# Sheet2.net
KiCad netlist of a schematic drawn in Altium Designer
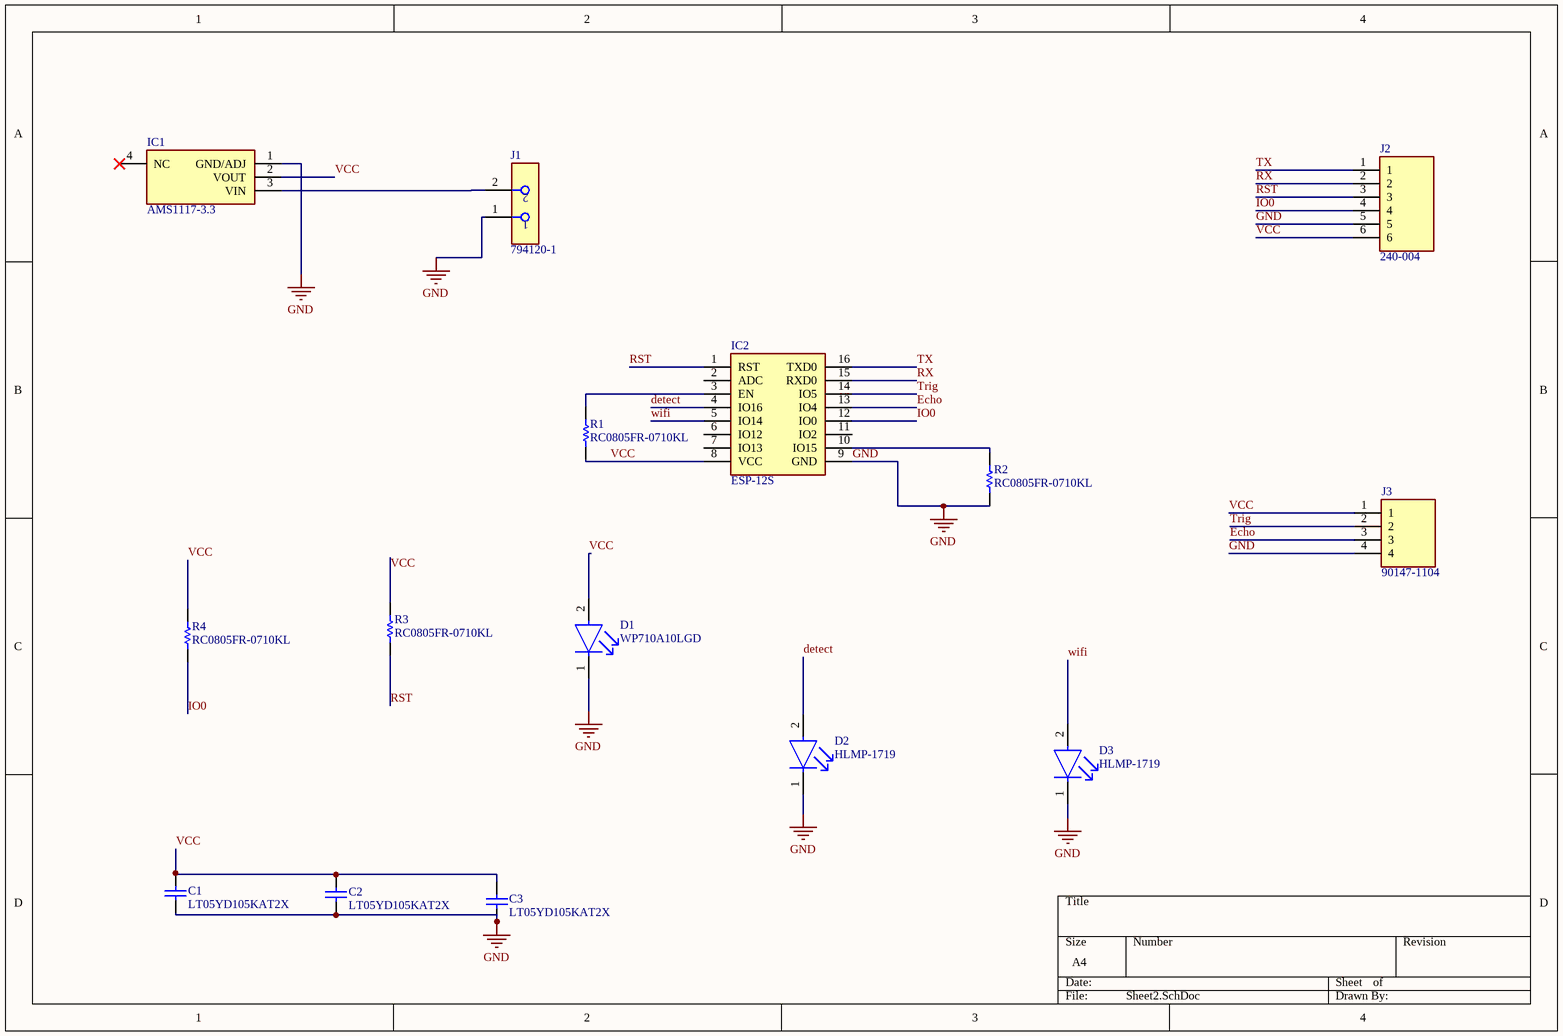
[diagram p0: Sheet2.SchDoc]

(export (version "E")
  (design (tool "Eeschema 10.0.6"))
  (components
    (comp (ref "C1")
      (value "LT05YD105KAT2X")
      (footprint "CAPC2013X130X50NL20T25")
      (fields (field (name "MANUFACTURER") "AVX Interconnect / Elco"))
      (libsource (lib "Altium Content Vault") (part "CAP"))
    )
    (comp (ref "C2")
      (value "LT05YD105KAT2X")
      (footprint "CAPC2013X130X50NL20T25")
      (fields (field (name "MANUFACTURER") "AVX Interconnect / Elco"))
      (libsource (lib "Altium Content Vault") (part "CAP"))
    )
    (comp (ref "C3")
      (value "LT05YD105KAT2X")
      (footprint "CAPC2013X130X50NL20T25")
      (fields (field (name "MANUFACTURER") "AVX Interconnect / Elco"))
      (libsource (lib "Altium Content Vault") (part "CAP"))
    )
    (comp (ref "D1")
      (value "WP710A10LGD")
      (footprint "FP-WP710A10LGD-MFG")
      (description "WP710A10LGD LED Thru-Hole PCB Green T-1 3mm Green Lens 2 mA 568 nm 2 mcd Round")
      (libsource (lib "Altium Content Vault") (part "8706943c75ba83719d021d2fdc84c58"))
    )
    (comp (ref "D2")
      (value "HLMP-1719")
      (footprint "FP-HLMP-1719-MFG")
      (description "LED YELLOW DIFFUSED T-1 T/H")
      (fields
        (field (name "MANUFACTURER") "Broadcom")
        (field (name "OCTOPART") "https://octopart.com/hlmp-1719-broadcom-71130405")
      )
      (libsource (lib "Altium Content Vault") (part "8706943c75ba83719d021d2fdc84c58"))
    )
    (comp (ref "D3")
      (value "HLMP-1719")
      (footprint "FP-HLMP-1719-MFG")
      (description "LED YELLOW DIFFUSED T-1 T/H")
      (fields
        (field (name "MANUFACTURER") "Broadcom")
        (field (name "OCTOPART") "https://octopart.com/hlmp-1719-broadcom-71130405")
      )
      (libsource (lib "Altium Content Vault") (part "8706943c75ba83719d021d2fdc84c58"))
    )
    (comp (ref "IC1")
      (value "AMS1117-3.3")
      (footprint "SamacSys:SOT229P700X180-4N")
      (description "Integrated Circuit")
      (libsource (lib "*") (part "AMS1117-3.3"))
    )
    (comp (ref "IC2")
      (value "ESP-12S")
      (footprint "SamacSys:ESP12S")
      (description "Integrated Circuit")
      (fields (field (name "MOUSER PART NUMBER") "223-ESP-12S"))
      (libsource (lib "*") (part "ESP-12S"))
    )
    (comp (ref "J1")
      (value "794120-1")
      (footprint "FP-794120-1-MFG")
      (description "794120-1 Power Connector, 2 Contact(s), Male, Solder Terminal, Receptacle")
      (libsource (lib "Altium Content Vault") (part "78f693cf7826bc156400b272d5a8ffe"))
    )
    (comp (ref "J2")
      (value "240-004")
      (footprint "SamacSys:HDRV6W64P0X254_1X6_1524X254X909P")
      (description "Connector")
      (libsource (lib "*") (part "240-004"))
    )
    (comp (ref "J3")
      (value "90147-1104")
      (footprint "SamacSys:RHDR4W70P0X254_1X4_1016X244X870P")
      (description "Connector")
      (fields (field (name "MOUSER PART NUMBER") "538-90147-1104"))
      (libsource (lib "*") (part "90147-1104"))
    )
    (comp (ref "R1")
      (value "RC0805FR-0710KL")
      (footprint "RESC2013X60X35NL10T20")
      (description "Chip Resistor, 10 KOhm, +/- 1%, 0.125 W, -55 to 155 degC, 0805 (2012 Metric), RoHS, Tape and Reel")
      (fields (field (name "MANUFACTURER") "Yageo"))
      (libsource (lib "Altium Content Vault") (part "RES-2"))
    )
    (comp (ref "R2")
      (value "RC0805FR-0710KL")
      (footprint "RESC2013X60X35NL10T20")
      (description "Chip Resistor, 10 KOhm, +/- 1%, 0.125 W, -55 to 155 degC, 0805 (2012 Metric), RoHS, Tape and Reel")
      (fields (field (name "MANUFACTURER") "Yageo"))
      (libsource (lib "Altium Content Vault") (part "RES-2"))
    )
    (comp (ref "R3")
      (value "RC0805FR-0710KL")
      (footprint "RESC2013X60X35NL10T20")
      (description "Chip Resistor, 10 KOhm, +/- 1%, 0.125 W, -55 to 155 degC, 0805 (2012 Metric), RoHS, Tape and Reel")
      (fields (field (name "MANUFACTURER") "Yageo"))
      (libsource (lib "Altium Content Vault") (part "RES-2"))
    )
    (comp (ref "R4")
      (value "RC0805FR-0710KL")
      (footprint "RESC2013X60X35NL10T20")
      (description "Chip Resistor, 10 KOhm, +/- 1%, 0.125 W, -55 to 155 degC, 0805 (2012 Metric), RoHS, Tape and Reel")
      (fields (field (name "MANUFACTURER") "Yageo"))
      (libsource (lib "Altium Content Vault") (part "RES-2"))
    )
  )
  (nets
    (net (code "1") (name "/Echo") (class "Default")
      (node (ref "IC2") (pin "13") (pinfunction "IO4_13") (pintype "passive"))
      (node (ref "J3") (pin "3") (pinfunction "3_3") (pintype "passive"))
    )
    (net (code "2") (name "/IO0") (class "Default")
      (node (ref "IC2") (pin "12") (pinfunction "IO0_12") (pintype "passive"))
      (node (ref "J2") (pin "4") (pinfunction "4_4") (pintype "passive"))
      (node (ref "R4") (pin "1") (pinfunction "1_1") (pintype "passive"))
    )
    (net (code "3") (name "/RST") (class "Default")
      (node (ref "IC2") (pin "1") (pinfunction "RST_1") (pintype "passive"))
      (node (ref "J2") (pin "3") (pinfunction "3_3") (pintype "passive"))
      (node (ref "R3") (pin "1") (pinfunction "1_1") (pintype "passive"))
    )
    (net (code "4") (name "/RX") (class "Default")
      (node (ref "IC2") (pin "15") (pinfunction "RXD0_15") (pintype "passive"))
      (node (ref "J2") (pin "2") (pinfunction "2_2") (pintype "passive"))
    )
    (net (code "5") (name "/TX") (class "Default")
      (node (ref "IC2") (pin "16") (pinfunction "TXD0_16") (pintype "passive"))
      (node (ref "J2") (pin "1") (pinfunction "1_1") (pintype "passive"))
    )
    (net (code "6") (name "/Trig") (class "Default")
      (node (ref "IC2") (pin "14") (pinfunction "IO5_14") (pintype "passive"))
      (node (ref "J3") (pin "2") (pinfunction "2_2") (pintype "passive"))
    )
    (net (code "7") (name "/VCC") (class "Default")
      (node (ref "C1") (pin "2") (pinfunction "2_2") (pintype "passive"))
      (node (ref "C2") (pin "2") (pinfunction "2_2") (pintype "passive"))
      (node (ref "C3") (pin "2") (pinfunction "2_2") (pintype "passive"))
      (node (ref "D1") (pin "2") (pinfunction "A_2") (pintype "passive"))
      (node (ref "IC1") (pin "2") (pinfunction "VOUT_2") (pintype "passive"))
      (node (ref "IC2") (pin "8") (pinfunction "VCC_8") (pintype "passive"))
      (node (ref "J2") (pin "6") (pinfunction "6_6") (pintype "passive"))
      (node (ref "J3") (pin "1") (pinfunction "1_1") (pintype "passive"))
      (node (ref "R1") (pin "1") (pinfunction "1_1") (pintype "passive"))
      (node (ref "R3") (pin "2") (pinfunction "2_2") (pintype "passive"))
      (node (ref "R4") (pin "2") (pinfunction "2_2") (pintype "passive"))
    )
    (net (code "8") (name "/detect") (class "Default")
      (node (ref "D2") (pin "2") (pinfunction "A_2") (pintype "passive"))
      (node (ref "IC2") (pin "4") (pinfunction "IO16_4") (pintype "passive"))
    )
    (net (code "9") (name "/wifi") (class "Default")
      (node (ref "D3") (pin "2") (pinfunction "A_2") (pintype "passive"))
      (node (ref "IC2") (pin "5") (pinfunction "IO14_5") (pintype "passive"))
    )
    (net (code "10") (name "GND") (class "Default")
      (node (ref "C1") (pin "1") (pinfunction "1_1") (pintype "passive"))
      (node (ref "C2") (pin "1") (pinfunction "1_1") (pintype "passive"))
      (node (ref "C3") (pin "1") (pinfunction "1_1") (pintype "passive"))
      (node (ref "D1") (pin "1") (pinfunction "C_1") (pintype "passive"))
      (node (ref "D2") (pin "1") (pinfunction "C_1") (pintype "passive"))
      (node (ref "D3") (pin "1") (pinfunction "C_1") (pintype "passive"))
      (node (ref "IC1") (pin "1") (pinfunction "GND/ADJ_1") (pintype "passive"))
      (node (ref "IC2") (pin "9") (pinfunction "GND_9") (pintype "passive"))
      (node (ref "J1") (pin "1") (pinfunction "1_1") (pintype "passive"))
      (node (ref "J2") (pin "5") (pinfunction "5_5") (pintype "passive"))
      (node (ref "J3") (pin "4") (pinfunction "4_4") (pintype "passive"))
      (node (ref "R2") (pin "1") (pinfunction "1_1") (pintype "passive"))
    )
    (net (code "11") (name "Net-(IC1-VIN)") (class "Default")
      (node (ref "IC1") (pin "3") (pinfunction "VIN_3") (pintype "passive"))
      (node (ref "J1") (pin "2") (pinfunction "2_2") (pintype "passive"))
    )
    (net (code "12") (name "Net-(IC2-EN)") (class "Default")
      (node (ref "IC2") (pin "3") (pinfunction "EN_3") (pintype "passive"))
      (node (ref "R1") (pin "2") (pinfunction "2_2") (pintype "passive"))
    )
    (net (code "13") (name "Net-(IC2-IO15)") (class "Default")
      (node (ref "IC2") (pin "10") (pinfunction "IO15_10") (pintype "passive"))
      (node (ref "R2") (pin "2") (pinfunction "2_2") (pintype "passive"))
    )
    (net (code "14") (name "unconnected-(IC1-NC-Pad4)") (class "Default")
      (node (ref "IC1") (pin "4") (pinfunction "NC_4") (pintype "passive+no_connect"))
    )
    (net (code "15") (name "unconnected-(IC2-ADC-Pad2)") (class "Default")
      (node (ref "IC2") (pin "2") (pinfunction "ADC_2") (pintype "passive"))
    )
    (net (code "16") (name "unconnected-(IC2-IO2-Pad11)") (class "Default")
      (node (ref "IC2") (pin "11") (pinfunction "IO2_11") (pintype "passive"))
    )
    (net (code "17") (name "unconnected-(IC2-IO12-Pad6)") (class "Default")
      (node (ref "IC2") (pin "6") (pinfunction "IO12_6") (pintype "passive"))
    )
    (net (code "18") (name "unconnected-(IC2-IO13-Pad7)") (class "Default")
      (node (ref "IC2") (pin "7") (pinfunction "IO13_7") (pintype "passive"))
    )
  )
)
